# main.net
KiCad netlist of a schematic drawn in Altium Designer
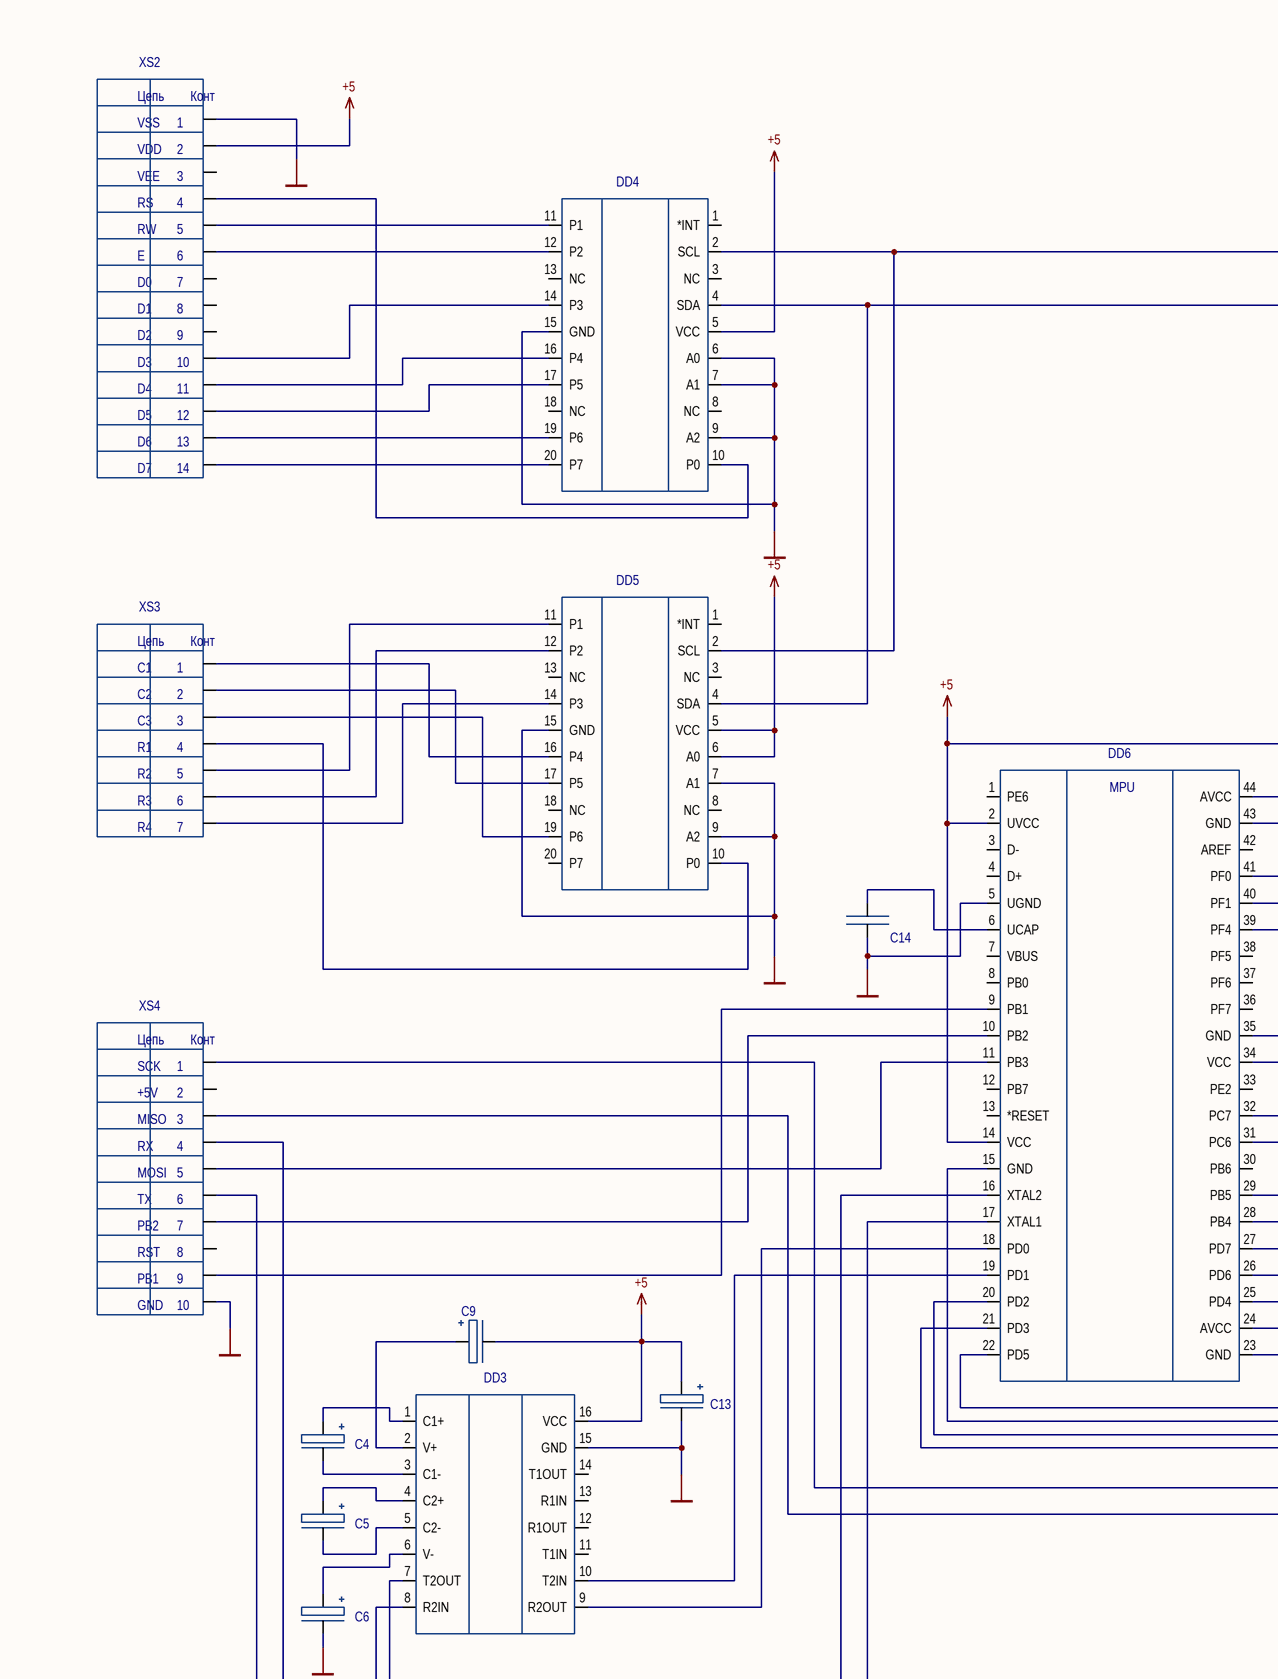
[diagram p0: main.SchDoc, top left]
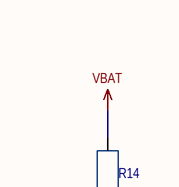
[diagram p1: main.SchDoc, top right]
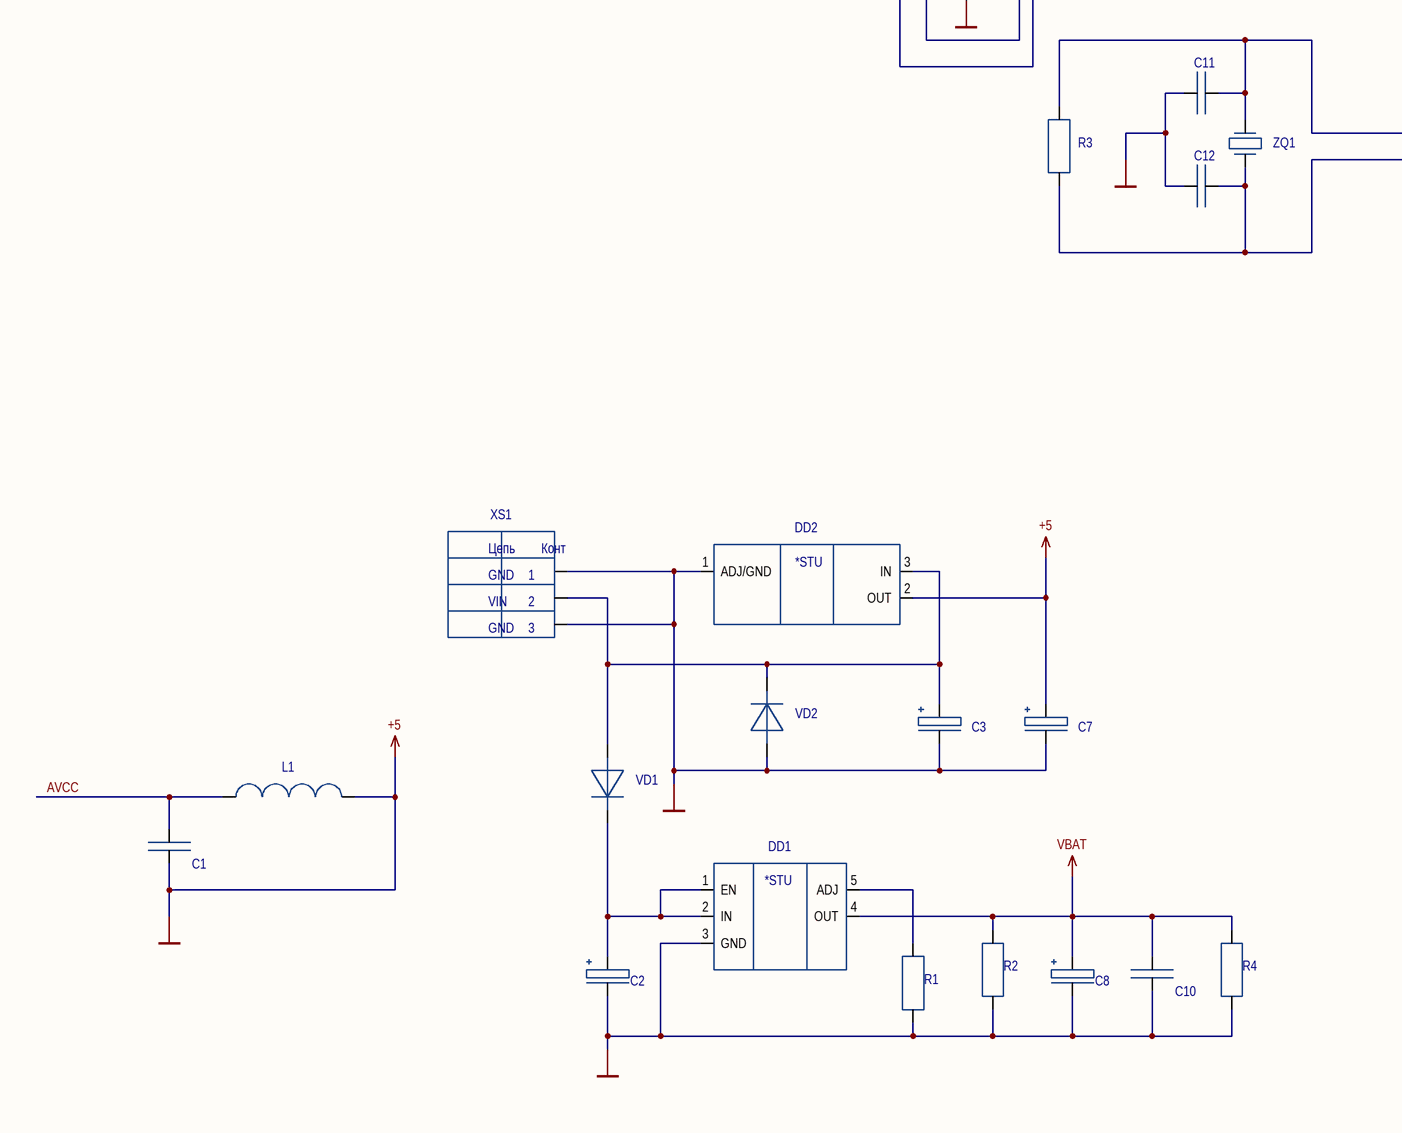
[diagram p2: main.SchDoc, bottom left]
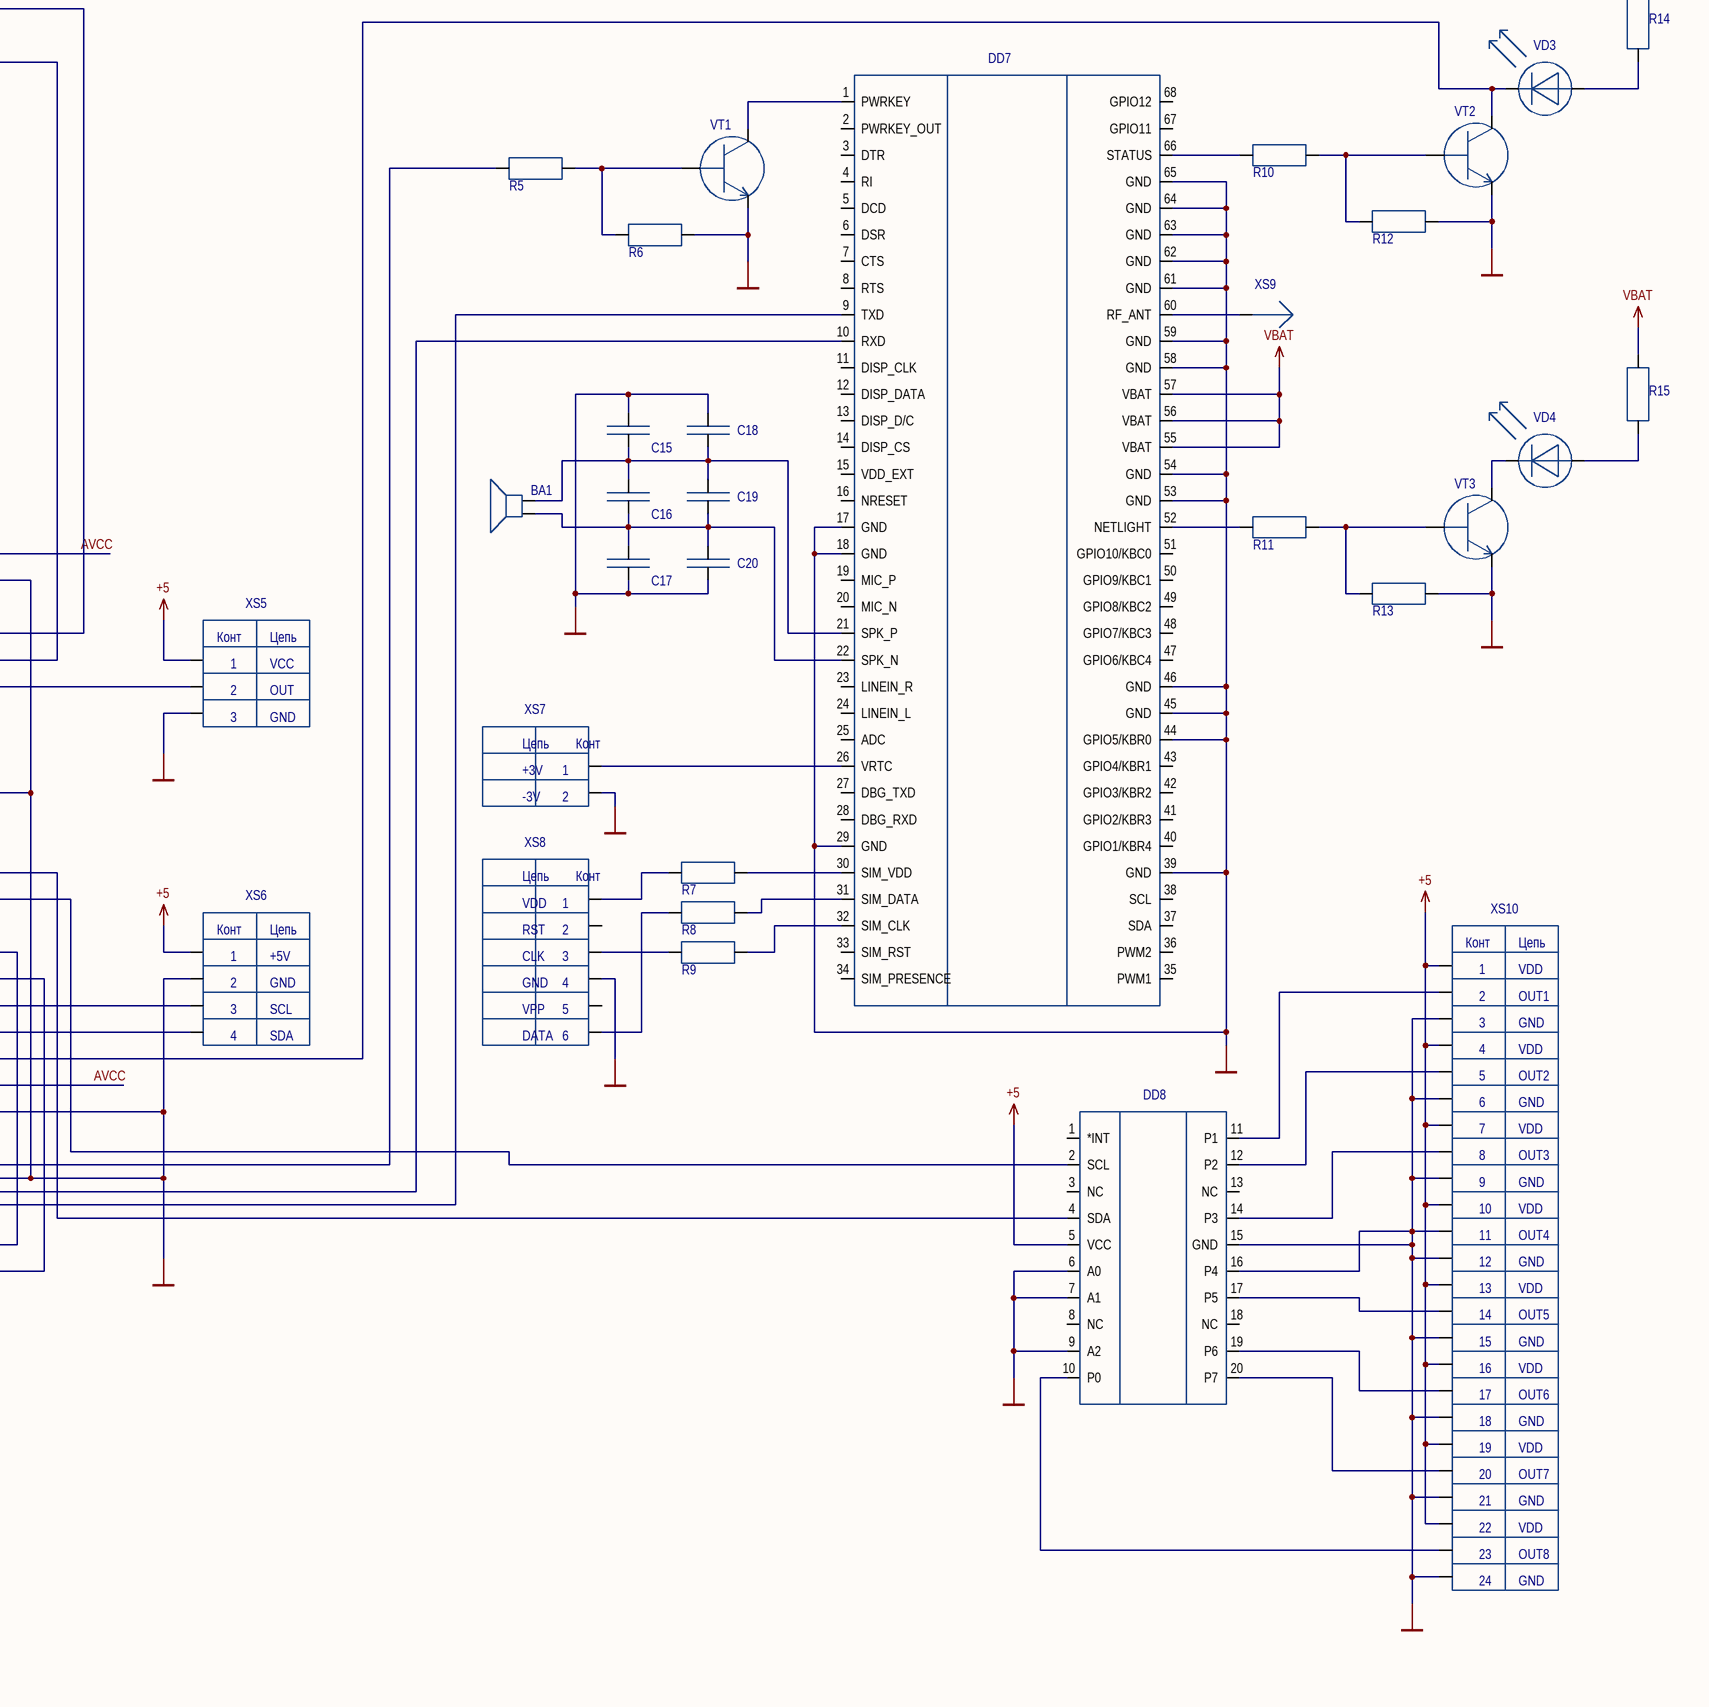
[diagram p3: main.SchDoc, bottom right]

(export (version "E")
  (design (tool "Eeschema 10.0.6"))
  (components
    (comp (ref "BA1") (value "beeper_HPA17F") (libsource (lib "diploma") (part "beeper_HPA17F")))
    (comp (ref "C1") (value "cap_1mkF") (libsource (lib "diploma") (part "cap_1mkF")))
    (comp (ref "C2") (value "cap_pol_100mkF") (libsource (lib "diploma") (part "cap_pol_100mkF")))
    (comp (ref "C3") (value "pol_10mkF") (libsource (lib "diploma") (part "cap_pol_10mkF")))
    (comp (ref "C4") (value "pol_1mkF") (libsource (lib "diploma") (part "cap_pol_1mkF")))
    (comp (ref "C5") (value "pol_1mkF") (libsource (lib "diploma") (part "cap_pol_1mkF")))
    (comp (ref "C6") (value "pol_1mkF") (libsource (lib "diploma") (part "cap_pol_1mkF")))
    (comp (ref "C7") (value "pol_10mkF") (libsource (lib "diploma") (part "cap_pol_10mkF")))
    (comp (ref "C8") (value "cap_pol_100mkF") (libsource (lib "diploma") (part "cap_pol_100mkF")))
    (comp (ref "C9") (value "pol_1mkF") (libsource (lib "diploma") (part "cap_pol_1mkF")))
    (comp (ref "C10") (value "cap_100nF") (libsource (lib "diploma") (part "cap_100nF")))
    (comp (ref "C11") (value "33pF") (libsource (lib "diploma") (part "cap_33pF")))
    (comp (ref "C12") (value "33pF") (libsource (lib "diploma") (part "cap_33pF")))
    (comp (ref "C13") (value "pol_1mkF") (libsource (lib "diploma") (part "cap_pol_1mkF")))
    (comp (ref "C14") (value "cap_1mkF") (libsource (lib "diploma") (part "cap_1mkF")))
    (comp (ref "C15") (value "cap_10pF") (libsource (lib "diploma") (part "cap_10pF")))
    (comp (ref "C16") (value "cap_10pF") (libsource (lib "diploma") (part "cap_10pF")))
    (comp (ref "C17") (value "cap_10pF") (libsource (lib "diploma") (part "cap_10pF")))
    (comp (ref "C18") (value "cap_33pF") (libsource (lib "diploma") (part "cap_33pF")))
    (comp (ref "C19") (value "cap_33pF") (libsource (lib "diploma") (part "cap_33pF")))
    (comp (ref "C20") (value "cap_33pF") (libsource (lib "diploma") (part "cap_33pF")))
    (comp (ref "DD1") (value "stu_MIC29302WT") (libsource (lib "diploma") (part "stu_MIC29302WT")))
    (comp (ref "DD2")
      (value "NCP1117ST50T3G")
      (footprint "SOT223-3_ONS")
      (description "No Description Available")
      (libsource (lib "NCP1117ST50T3G") (part "NCP1117ST50T3G"))
    )
    (comp (ref "DD3")
      (value "MAX232CSE+")
      (footprint "max232:21-0041_S16+3_MXM")
      (description "No Description Available")
      (libsource (lib "max232") (part "MAX232CSE+"))
    )
    (comp (ref "DD4")
      (value "PCF8574DGVR")
      (footprint "PCF8574DGVR:DGV20")
      (description "Remote 8-Bit I/O Expander for I2C-Bus")
      (fields
        (field (name "MANUFACTURER") "Texas Instruments")
        (field (name "GENERIC_PART_NUMBER") "PCF8574")
      )
      (libsource (lib "") (part "PCF8574DGVR_1"))
    )
    (comp (ref "DD5")
      (value "PCF8574DGVR")
      (footprint "PCF8574DGVR:DGV20")
      (description "Remote 8-Bit I/O Expander for I2C-Bus")
      (fields
        (field (name "MANUFACTURER") "Texas Instruments")
        (field (name "GENERIC_PART_NUMBER") "PCF8574")
      )
      (libsource (lib "") (part "PCF8574DGVR_1"))
    )
    (comp (ref "DD6")
      (value "ATMEGA32U4RC-AU")
      (footprint "44ML_ATM")
      (description "No Description Available")
      (libsource (lib "atmega32u4") (part "ATMEGA32U4RC-AU"))
    )
    (comp (ref "DD7") (value "SIM900A") (libsource (lib "diploma") (part "SIM900A")))
    (comp (ref "DD8")
      (value "PCF8574DGVR")
      (footprint "PCF8574DGVR:DGV20")
      (description "Remote 8-Bit I/O Expander for I2C-Bus")
      (fields
        (field (name "MANUFACTURER") "Texas Instruments")
        (field (name "GENERIC_PART_NUMBER") "PCF8574")
      )
      (libsource (lib "PCF8574DGVR") (part "PCF8574DGVR"))
    )
    (comp (ref "L1") (value "inductor_10uH") (libsource (lib "diploma") (part "inductor_10uH")))
    (comp (ref "R1") (value "res_47k") (libsource (lib "diploma") (part "res_47k")))
    (comp (ref "R2") (value "res_100K") (libsource (lib "diploma") (part "res_100K")))
    (comp (ref "R3") (value "res_1M") (libsource (lib "diploma") (part "res_1M")))
    (comp (ref "R4") (value "res_510") (libsource (lib "diploma") (part "res_510")))
    (comp (ref "R5") (value "res_4.7k") (libsource (lib "diploma") (part "res_4.7k")))
    (comp (ref "R6") (value "res_47k") (libsource (lib "") (part "res_47k_1")))
    (comp (ref "R7") (value "res_22") (libsource (lib "diploma") (part "res_22")))
    (comp (ref "R8") (value "res_22") (libsource (lib "diploma") (part "res_22")))
    (comp (ref "R9") (value "res_22") (libsource (lib "diploma") (part "res_22")))
    (comp (ref "R10") (value "res_4.7k") (libsource (lib "diploma") (part "res_4.7k")))
    (comp (ref "R11") (value "res_4.7k") (libsource (lib "diploma") (part "res_4.7k")))
    (comp (ref "R12") (value "res_47k") (libsource (lib "") (part "res_47k_1")))
    (comp (ref "R13") (value "res_47k") (libsource (lib "") (part "res_47k_1")))
    (comp (ref "R14") (value "res_510") (libsource (lib "diploma") (part "res_510")))
    (comp (ref "R15") (value "res_510") (libsource (lib "diploma") (part "res_510")))
    (comp (ref "VD1") (value "diode_M7") (libsource (lib "diploma") (part "diode_M7")))
    (comp (ref "VD2") (value "diode_M7") (libsource (lib "diploma") (part "diode_M7")))
    (comp (ref "VD3") (value "diode_red") (libsource (lib "diploma") (part "diode_red")))
    (comp (ref "VD4") (value "diode_red") (libsource (lib "diploma") (part "diode_red")))
    (comp (ref "VT1") (value "BC547") (libsource (lib "diploma") (part "BC547")))
    (comp (ref "VT2") (value "BC547") (libsource (lib "diploma") (part "BC547")))
    (comp (ref "VT3") (value "BC547") (libsource (lib "diploma") (part "BC547")))
    (comp (ref "XS1") (value "power_supply_jack") (libsource (lib "diploma") (part "power_supply_jack")))
    (comp (ref "XS2") (value "LCD_connector") (libsource (lib "diploma") (part "LCD_connector")))
    (comp (ref "XS3") (value "conn_Keypad") (libsource (lib "diploma") (part "conn_Keypad")))
    (comp (ref "XS4") (value "BH-10") (libsource (lib "diploma") (part "RS-232")))
    (comp (ref "XS5") (value "VS1833B") (libsource (lib "diploma") (part "VS1833B")))
    (comp (ref "XS6") (value "usb_typeA") (libsource (lib "diploma") (part "usb_typeA")))
    (comp (ref "XS7") (value "conn_Battery_CR2032") (libsource (lib "diploma") (part "conn_Battery_CR2032")))
    (comp (ref "XS8")
      (value "SIM5051-6-0-18-00-A")
      (footprint "sim_connector:SIM5051-6-0-18-00-A_GCT")
      (description "No Description Available")
      (libsource (lib "sim_connector") (part "SIM5051-6-0-18-00-A"))
    )
    (comp (ref "XS9") (value "antenn_connector") (libsource (lib "diploma") (part "antenn_connector")))
    (comp (ref "XS10") (value "ds1013") (libsource (lib "diploma") (part "temperature_sensors_connector")))
    (comp (ref "ZQ1") (value "crystal_8mhz") (libsource (lib "diploma") (part "crystal_8mhz")))
  )
  (nets
    (net (code "1") (name "+5") (class "Default")
      (node (ref "C1") (pin "1") (pinfunction "1_1") (pintype "passive"))
      (node (ref "C10") (pin "1") (pinfunction "1_1") (pintype "passive"))
      (node (ref "C11") (pin "2") (pinfunction "2_2") (pintype "passive"))
      (node (ref "C12") (pin "2") (pinfunction "2_2") (pintype "passive"))
      (node (ref "C13") (pin "1") (pinfunction "1_1") (pintype "passive"))
      (node (ref "C13") (pin "2") (pinfunction "2_2") (pintype "passive"))
      (node (ref "C15") (pin "2") (pinfunction "2_2") (pintype "passive"))
      (node (ref "C17") (pin "1") (pinfunction "1_1") (pintype "passive"))
      (node (ref "C18") (pin "2") (pinfunction "2_2") (pintype "passive"))
      (node (ref "C2") (pin "1") (pinfunction "1_1") (pintype "passive"))
      (node (ref "C20") (pin "1") (pinfunction "1_1") (pintype "passive"))
      (node (ref "C3") (pin "1") (pinfunction "1_1") (pintype "passive"))
      (node (ref "C6") (pin "1") (pinfunction "1_1") (pintype "passive"))
      (node (ref "C7") (pin "1") (pinfunction "1_1") (pintype "passive"))
      (node (ref "C7") (pin "2") (pinfunction "2_2") (pintype "passive"))
      (node (ref "C8") (pin "1") (pinfunction "1_1") (pintype "passive"))
      (node (ref "C9") (pin "1") (pinfunction "1_1") (pintype "passive"))
      (node (ref "DD1") (pin "3") (pinfunction "GND_3") (pintype "passive"))
      (node (ref "DD2") (pin "1") (pinfunction "ADJ/GND_1") (pintype "passive"))
      (node (ref "DD2") (pin "2") (pinfunction "OUT_2") (pintype "passive"))
      (node (ref "DD3") (pin "15") (pinfunction "GND_15") (pintype "passive"))
      (node (ref "DD3") (pin "16") (pinfunction "VCC_16") (pintype "passive"))
      (node (ref "DD4") (pin "15") (pinfunction "GND_15") (pintype "passive"))
      (node (ref "DD4") (pin "5") (pinfunction "VCC_5") (pintype "passive"))
      (node (ref "DD4") (pin "6") (pinfunction "A0_6") (pintype "passive"))
      (node (ref "DD4") (pin "7") (pinfunction "A1_7") (pintype "passive"))
      (node (ref "DD4") (pin "9") (pinfunction "A2_9") (pintype "passive"))
      (node (ref "DD5") (pin "15") (pinfunction "GND_15") (pintype "passive"))
      (node (ref "DD5") (pin "5") (pinfunction "VCC_5") (pintype "passive"))
      (node (ref "DD5") (pin "6") (pinfunction "A0_6") (pintype "passive"))
      (node (ref "DD5") (pin "7") (pinfunction "A1_7") (pintype "passive"))
      (node (ref "DD5") (pin "9") (pinfunction "A2_9") (pintype "passive"))
      (node (ref "DD6") (pin "14") (pinfunction "VCC_14") (pintype "passive"))
      (node (ref "DD6") (pin "15") (pinfunction "GND_15") (pintype "passive"))
      (node (ref "DD6") (pin "2") (pinfunction "UVCC_2") (pintype "passive"))
      (node (ref "DD6") (pin "23") (pinfunction "GND_23") (pintype "passive"))
      (node (ref "DD6") (pin "34") (pinfunction "VCC_34") (pintype "passive"))
      (node (ref "DD6") (pin "35") (pinfunction "GND_35") (pintype "passive"))
      (node (ref "DD6") (pin "43") (pinfunction "GND_43") (pintype "passive"))
      (node (ref "DD7") (pin "17") (pinfunction "GND_17") (pintype "passive"))
      (node (ref "DD7") (pin "18") (pinfunction "GND_18") (pintype "passive"))
      (node (ref "DD7") (pin "29") (pinfunction "GND_29") (pintype "passive"))
      (node (ref "DD7") (pin "39") (pinfunction "GND_39") (pintype "passive"))
      (node (ref "DD7") (pin "44") (pinfunction "GPIO5/KBR0_44") (pintype "passive"))
      (node (ref "DD7") (pin "45") (pinfunction "GND_45") (pintype "passive"))
      (node (ref "DD7") (pin "46") (pinfunction "GND_46") (pintype "passive"))
      (node (ref "DD7") (pin "53") (pinfunction "GND_53") (pintype "passive"))
      (node (ref "DD7") (pin "54") (pinfunction "GND_54") (pintype "passive"))
      (node (ref "DD7") (pin "58") (pinfunction "GND_58") (pintype "passive"))
      (node (ref "DD7") (pin "59") (pinfunction "GND_59") (pintype "passive"))
      (node (ref "DD7") (pin "61") (pinfunction "GND_61") (pintype "passive"))
      (node (ref "DD7") (pin "62") (pinfunction "GND_62") (pintype "passive"))
      (node (ref "DD7") (pin "63") (pinfunction "GND_63") (pintype "passive"))
      (node (ref "DD7") (pin "64") (pinfunction "GND_64") (pintype "passive"))
      (node (ref "DD7") (pin "65") (pinfunction "GND_65") (pintype "passive"))
      (node (ref "DD8") (pin "15") (pinfunction "GND_15") (pintype "passive"))
      (node (ref "DD8") (pin "16") (pinfunction "P4_16") (pintype "passive"))
      (node (ref "DD8") (pin "5") (pinfunction "VCC_5") (pintype "passive"))
      (node (ref "DD8") (pin "6") (pinfunction "A0_6") (pintype "passive"))
      (node (ref "DD8") (pin "7") (pinfunction "A1_7") (pintype "passive"))
      (node (ref "DD8") (pin "9") (pinfunction "A2_9") (pintype "passive"))
      (node (ref "L1") (pin "2") (pinfunction "2_2") (pintype "passive"))
      (node (ref "R1") (pin "1") (pinfunction "1_1") (pintype "passive"))
      (node (ref "R12") (pin "2") (pinfunction "2_2") (pintype "passive"))
      (node (ref "R13") (pin "2") (pinfunction "2_2") (pintype "passive"))
      (node (ref "R2") (pin "1") (pinfunction "1_1") (pintype "passive"))
      (node (ref "R4") (pin "1") (pinfunction "1_1") (pintype "passive"))
      (node (ref "R6") (pin "2") (pinfunction "2_2") (pintype "passive"))
      (node (ref "VD2") (pin "1") (pinfunction "1_1") (pintype "passive"))
      (node (ref "VT1") (pin "1") (pinfunction "E_1") (pintype "passive"))
      (node (ref "VT2") (pin "1") (pinfunction "E_1") (pintype "passive"))
      (node (ref "VT3") (pin "1") (pinfunction "E_1") (pintype "passive"))
      (node (ref "XS1") (pin "1") (pinfunction "+5V_1") (pintype "passive"))
      (node (ref "XS1") (pin "3") (pinfunction "SCL_3") (pintype "passive"))
      (node (ref "XS10") (pin "1") (pinfunction "VSS_1") (pintype "passive"))
      (node (ref "XS10") (pin "10") (pinfunction "D3_10") (pintype "passive"))
      (node (ref "XS10") (pin "11") (pinfunction "D4_11") (pintype "passive"))
      (node (ref "XS10") (pin "12") (pinfunction "D5_12") (pintype "passive"))
      (node (ref "XS10") (pin "13") (pinfunction "D6_13") (pintype "passive"))
      (node (ref "XS10") (pin "15") (pinfunction "15_15") (pintype "passive"))
      (node (ref "XS10") (pin "16") (pinfunction "16_16") (pintype "passive"))
      (node (ref "XS10") (pin "18") (pinfunction "18_18") (pintype "passive"))
      (node (ref "XS10") (pin "19") (pinfunction "19_19") (pintype "passive"))
      (node (ref "XS10") (pin "21") (pinfunction "21_21") (pintype "passive"))
      (node (ref "XS10") (pin "22") (pinfunction "22_22") (pintype "passive"))
      (node (ref "XS10") (pin "24") (pinfunction "24_24") (pintype "passive"))
      (node (ref "XS10") (pin "3") (pinfunction "VO_3") (pintype "passive"))
      (node (ref "XS10") (pin "4") (pinfunction "C/D_4") (pintype "passive"))
      (node (ref "XS10") (pin "6") (pinfunction "*WR_6") (pintype "passive"))
      (node (ref "XS10") (pin "7") (pinfunction "D0_7") (pintype "passive"))
      (node (ref "XS10") (pin "9") (pinfunction "D2_9") (pintype "passive"))
      (node (ref "XS2") (pin "1") (pinfunction "VSS_1") (pintype "passive"))
      (node (ref "XS2") (pin "2") (pinfunction "VDD_2") (pintype "passive"))
      (node (ref "XS4") (pin "10") (pinfunction "D3_10") (pintype "passive"))
      (node (ref "XS5") (pin "1") (pinfunction "VCC_1") (pintype "passive"))
      (node (ref "XS5") (pin "3") (pinfunction "GND_3") (pintype "passive"))
      (node (ref "XS6") (pin "1") (pinfunction "+5V_1") (pintype "passive"))
      (node (ref "XS6") (pin "2") (pinfunction "GND_2") (pintype "passive"))
      (node (ref "XS7") (pin "2") (pinfunction "2_2") (pintype "passive"))
      (node (ref "XS8") (pin "4") (pinfunction "GND_4") (pintype "passive"))
    )
    (net (code "2") (name "/AVCC") (class "Default")
      (node (ref "C1") (pin "2") (pinfunction "2_2") (pintype "passive"))
      (node (ref "DD6") (pin "24") (pinfunction "AVCC_24") (pintype "passive"))
      (node (ref "DD6") (pin "44") (pinfunction "AVCC_44") (pintype "passive"))
      (node (ref "L1") (pin "1") (pinfunction "1_1") (pintype "passive"))
    )
    (net (code "3") (name "Net-(DD1-ADJ)") (class "Default")
      (node (ref "DD1") (pin "5") (pinfunction "ADJ_5") (pintype "passive"))
      (node (ref "R1") (pin "2") (pinfunction "2_2") (pintype "passive"))
    )
    (net (code "4") (name "Net-(DD1-EN)") (class "Default")
      (node (ref "C2") (pin "2") (pinfunction "2_2") (pintype "passive"))
      (node (ref "DD1") (pin "1") (pinfunction "EN_1") (pintype "passive"))
      (node (ref "DD1") (pin "2") (pinfunction "IN_2") (pintype "passive"))
      (node (ref "VD1") (pin "2") (pinfunction "2_2") (pintype "passive"))
    )
    (net (code "5") (name "Net-(DD2-IN)") (class "Default")
      (node (ref "C3") (pin "2") (pinfunction "2_2") (pintype "passive"))
      (node (ref "DD2") (pin "3") (pinfunction "IN_3") (pintype "passive"))
      (node (ref "VD1") (pin "1") (pinfunction "1_1") (pintype "passive"))
      (node (ref "VD2") (pin "2") (pinfunction "2_2") (pintype "passive"))
      (node (ref "XS1") (pin "2") (pinfunction "GND_2") (pintype "passive"))
    )
    (net (code "6") (name "Net-(DD3-C1+)") (class "Default")
      (node (ref "C4") (pin "2") (pinfunction "2_2") (pintype "passive"))
      (node (ref "DD3") (pin "1") (pinfunction "C1+_1") (pintype "passive"))
    )
    (net (code "7") (name "Net-(DD3-C1-)") (class "Default")
      (node (ref "C4") (pin "1") (pinfunction "1_1") (pintype "passive"))
      (node (ref "DD3") (pin "3") (pinfunction "C1-_3") (pintype "passive"))
    )
    (net (code "8") (name "Net-(DD3-C2+)") (class "Default")
      (node (ref "C5") (pin "2") (pinfunction "2_2") (pintype "passive"))
      (node (ref "DD3") (pin "4") (pinfunction "C2+_4") (pintype "passive"))
    )
    (net (code "9") (name "Net-(DD3-C2-)") (class "Default")
      (node (ref "C5") (pin "1") (pinfunction "1_1") (pintype "passive"))
      (node (ref "DD3") (pin "5") (pinfunction "C2-_5") (pintype "passive"))
    )
    (net (code "10") (name "Net-(DD3-R2IN)") (class "Default")
      (node (ref "DD3") (pin "8") (pinfunction "R2IN_8") (pintype "passive"))
      (node (ref "XS4") (pin "4") (pinfunction "C/D_4") (pintype "passive"))
    )
    (net (code "11") (name "Net-(DD3-R2OUT)") (class "Default")
      (node (ref "DD3") (pin "9") (pinfunction "R2OUT_9") (pintype "passive"))
      (node (ref "DD6") (pin "18") (pinfunction "PD0_18") (pintype "passive"))
    )
    (net (code "12") (name "Net-(DD3-T2IN)") (class "Default")
      (node (ref "DD3") (pin "10") (pinfunction "T2IN_10") (pintype "passive"))
      (node (ref "DD6") (pin "19") (pinfunction "PD1_19") (pintype "passive"))
    )
    (net (code "13") (name "Net-(DD3-T2OUT)") (class "Default")
      (node (ref "DD3") (pin "7") (pinfunction "T2OUT_7") (pintype "passive"))
      (node (ref "XS4") (pin "6") (pinfunction "*WR_6") (pintype "passive"))
    )
    (net (code "14") (name "Net-(DD3-V+)") (class "Default")
      (node (ref "C9") (pin "2") (pinfunction "2_2") (pintype "passive"))
      (node (ref "DD3") (pin "2") (pinfunction "V+_2") (pintype "passive"))
    )
    (net (code "15") (name "Net-(DD3-V-)") (class "Default")
      (node (ref "C6") (pin "2") (pinfunction "2_2") (pintype "passive"))
      (node (ref "DD3") (pin "6") (pinfunction "V-_6") (pintype "passive"))
    )
    (net (code "16") (name "Net-(DD4-P0)") (class "Default")
      (node (ref "DD4") (pin "10") (pinfunction "P0_10") (pintype "passive"))
      (node (ref "XS2") (pin "4") (pinfunction "C/D_4") (pintype "passive"))
    )
    (net (code "17") (name "Net-(DD4-P1)") (class "Default")
      (node (ref "DD4") (pin "11") (pinfunction "P1_11") (pintype "passive"))
      (node (ref "XS2") (pin "5") (pinfunction "*RD_5") (pintype "passive"))
    )
    (net (code "18") (name "Net-(DD4-P2)") (class "Default")
      (node (ref "DD4") (pin "12") (pinfunction "P2_12") (pintype "passive"))
      (node (ref "XS2") (pin "6") (pinfunction "*WR_6") (pintype "passive"))
    )
    (net (code "19") (name "Net-(DD4-P3)") (class "Default")
      (node (ref "DD4") (pin "14") (pinfunction "P3_14") (pintype "passive"))
      (node (ref "XS2") (pin "10") (pinfunction "D3_10") (pintype "passive"))
    )
    (net (code "20") (name "Net-(DD4-P4)") (class "Default")
      (node (ref "DD4") (pin "16") (pinfunction "P4_16") (pintype "passive"))
      (node (ref "XS2") (pin "11") (pinfunction "D4_11") (pintype "passive"))
    )
    (net (code "21") (name "Net-(DD4-P5)") (class "Default")
      (node (ref "DD4") (pin "17") (pinfunction "P5_17") (pintype "passive"))
      (node (ref "XS2") (pin "12") (pinfunction "D5_12") (pintype "passive"))
    )
    (net (code "22") (name "Net-(DD4-P6)") (class "Default")
      (node (ref "DD4") (pin "19") (pinfunction "P6_19") (pintype "passive"))
      (node (ref "XS2") (pin "13") (pinfunction "D6_13") (pintype "passive"))
    )
    (net (code "23") (name "Net-(DD4-P7)") (class "Default")
      (node (ref "DD4") (pin "20") (pinfunction "P7_20") (pintype "passive"))
      (node (ref "XS2") (pin "14") (pinfunction "D7_14") (pintype "passive"))
    )
    (net (code "24") (name "Net-(DD4-SCL)") (class "Default")
      (node (ref "DD4") (pin "2") (pinfunction "SCL_2") (pintype "passive"))
      (node (ref "DD5") (pin "2") (pinfunction "SCL_2") (pintype "passive"))
      (node (ref "DD6") (pin "41") (pinfunction "PF0_41") (pintype "passive"))
    )
    (net (code "25") (name "Net-(DD4-SDA)") (class "Default")
      (node (ref "DD4") (pin "4") (pinfunction "SDA_4") (pintype "passive"))
      (node (ref "DD5") (pin "4") (pinfunction "SDA_4") (pintype "passive"))
      (node (ref "DD6") (pin "40") (pinfunction "PF1_40") (pintype "passive"))
    )
    (net (code "26") (name "Net-(DD5-P0)") (class "Default")
      (node (ref "DD5") (pin "10") (pinfunction "P0_10") (pintype "passive"))
      (node (ref "XS3") (pin "4") (pinfunction "C/D_4") (pintype "passive"))
    )
    (net (code "27") (name "Net-(DD5-P1)") (class "Default")
      (node (ref "DD5") (pin "11") (pinfunction "P1_11") (pintype "passive"))
      (node (ref "XS3") (pin "5") (pinfunction "*RD_5") (pintype "passive"))
    )
    (net (code "28") (name "Net-(DD5-P2)") (class "Default")
      (node (ref "DD5") (pin "12") (pinfunction "P2_12") (pintype "passive"))
      (node (ref "XS3") (pin "6") (pinfunction "*WR_6") (pintype "passive"))
    )
    (net (code "29") (name "Net-(DD5-P3)") (class "Default")
      (node (ref "DD5") (pin "14") (pinfunction "P3_14") (pintype "passive"))
      (node (ref "XS3") (pin "7") (pinfunction "D0_7") (pintype "passive"))
    )
    (net (code "30") (name "Net-(DD5-P4)") (class "Default")
      (node (ref "DD5") (pin "16") (pinfunction "P4_16") (pintype "passive"))
      (node (ref "XS3") (pin "1") (pinfunction "VSS_1") (pintype "passive"))
    )
    (net (code "31") (name "Net-(DD5-P5)") (class "Default")
      (node (ref "DD5") (pin "17") (pinfunction "P5_17") (pintype "passive"))
      (node (ref "XS3") (pin "2") (pinfunction "VDD_2") (pintype "passive"))
    )
    (net (code "32") (name "Net-(DD5-P6)") (class "Default")
      (node (ref "DD5") (pin "19") (pinfunction "P6_19") (pintype "passive"))
      (node (ref "XS3") (pin "3") (pinfunction "VO_3") (pintype "passive"))
    )
    (net (code "33") (name "Net-(DD6-PB1)") (class "Default")
      (node (ref "DD6") (pin "9") (pinfunction "PB1_9") (pintype "passive"))
      (node (ref "XS4") (pin "9") (pinfunction "D2_9") (pintype "passive"))
    )
    (net (code "34") (name "Net-(DD6-PB2)") (class "Default")
      (node (ref "DD6") (pin "10") (pinfunction "PB2_10") (pintype "passive"))
      (node (ref "XS4") (pin "7") (pinfunction "D0_7") (pintype "passive"))
    )
    (net (code "35") (name "Net-(DD6-PB3)") (class "Default")
      (node (ref "DD6") (pin "11") (pinfunction "PB3_11") (pintype "passive"))
      (node (ref "XS4") (pin "5") (pinfunction "*RD_5") (pintype "passive"))
    )
    (net (code "36") (name "Net-(DD6-PB4)") (class "Default")
      (node (ref "DD6") (pin "28") (pinfunction "PB4_28") (pintype "passive"))
      (node (ref "XS4") (pin "3") (pinfunction "VO_3") (pintype "passive"))
    )
    (net (code "37") (name "Net-(DD6-PB5)") (class "Default")
      (node (ref "DD6") (pin "29") (pinfunction "PB5_29") (pintype "passive"))
      (node (ref "XS4") (pin "1") (pinfunction "VSS_1") (pintype "passive"))
    )
    (net (code "38") (name "Net-(DD6-PC6)") (class "Default")
      (node (ref "DD6") (pin "31") (pinfunction "PC6_31") (pintype "passive"))
      (node (ref "DD8") (pin "2") (pinfunction "SCL_2") (pintype "passive"))
    )
    (net (code "39") (name "Net-(DD6-PC7)") (class "Default")
      (node (ref "DD6") (pin "32") (pinfunction "PC7_32") (pintype "passive"))
      (node (ref "DD8") (pin "4") (pinfunction "SDA_4") (pintype "passive"))
    )
    (net (code "40") (name "Net-(DD6-PD2)") (class "Default")
      (node (ref "DD6") (pin "20") (pinfunction "PD2_20") (pintype "passive"))
      (node (ref "DD7") (pin "10") (pinfunction "RXD_10") (pintype "passive"))
    )
    (net (code "41") (name "Net-(DD6-PD3)") (class "Default")
      (node (ref "DD6") (pin "21") (pinfunction "PD3_21") (pintype "passive"))
      (node (ref "DD7") (pin "9") (pinfunction "TXD_9") (pintype "passive"))
    )
    (net (code "42") (name "Net-(DD6-PD4)") (class "Default")
      (node (ref "DD6") (pin "25") (pinfunction "PD4_25") (pintype "passive"))
      (node (ref "VD3") (pin "2") (pinfunction "2_2") (pintype "passive"))
      (node (ref "VT2") (pin "3") (pinfunction "C_3") (pintype "passive"))
    )
    (net (code "43") (name "Net-(DD6-PD5)") (class "Default")
      (node (ref "DD6") (pin "22") (pinfunction "PD5_22") (pintype "passive"))
      (node (ref "R5") (pin "1") (pinfunction "1_1") (pintype "passive"))
    )
    (net (code "44") (name "Net-(DD6-PD6)") (class "Default")
      (node (ref "DD6") (pin "26") (pinfunction "PD6_26") (pintype "passive"))
      (node (ref "XS6") (pin "4") (pinfunction "SDA_4") (pintype "passive"))
    )
    (net (code "45") (name "Net-(DD6-PD7)") (class "Default")
      (node (ref "DD6") (pin "27") (pinfunction "PD7_27") (pintype "passive"))
      (node (ref "XS6") (pin "3") (pinfunction "SCL_3") (pintype "passive"))
    )
    (net (code "46") (name "Net-(DD6-PF4)") (class "Default")
      (node (ref "DD6") (pin "39") (pinfunction "PF4_39") (pintype "passive"))
      (node (ref "XS5") (pin "2") (pinfunction "OUT_2") (pintype "passive"))
    )
    (net (code "47") (name "Net-(DD6-UCAP)") (class "Default")
      (node (ref "C14") (pin "2") (pinfunction "2_2") (pintype "passive"))
      (node (ref "DD6") (pin "6") (pinfunction "UCAP_6") (pintype "passive"))
    )
    (net (code "48") (name "Net-(DD6-XTAL1)") (class "Default")
      (node (ref "C12") (pin "1") (pinfunction "1_1") (pintype "passive"))
      (node (ref "DD6") (pin "17") (pinfunction "XTAL1_17") (pintype "passive"))
      (node (ref "R3") (pin "1") (pinfunction "1_1") (pintype "passive"))
      (node (ref "ZQ1") (pin "1") (pinfunction "1_1") (pintype "passive"))
    )
    (net (code "49") (name "Net-(DD6-XTAL2)") (class "Default")
      (node (ref "C11") (pin "1") (pinfunction "1_1") (pintype "passive"))
      (node (ref "DD6") (pin "16") (pinfunction "XTAL2_16") (pintype "passive"))
      (node (ref "R3") (pin "2") (pinfunction "2_2") (pintype "passive"))
      (node (ref "ZQ1") (pin "2") (pinfunction "2_2") (pintype "passive"))
    )
    (net (code "50") (name "Net-(DD7-NETLIGHT)") (class "Default")
      (node (ref "DD7") (pin "52") (pinfunction "NETLIGHT_52") (pintype "passive"))
      (node (ref "R11") (pin "1") (pinfunction "1_1") (pintype "passive"))
    )
    (net (code "51") (name "Net-(DD7-PWRKEY)") (class "Default")
      (node (ref "DD7") (pin "1") (pinfunction "PWRKEY_1") (pintype "passive"))
      (node (ref "VT1") (pin "3") (pinfunction "C_3") (pintype "passive"))
    )
    (net (code "52") (name "Net-(DD7-RF_ANT)") (class "Default")
      (node (ref "DD7") (pin "60") (pinfunction "RF_ANT_60") (pintype "passive"))
      (node (ref "XS9") (pin "1") (pinfunction "1_1") (pintype "passive"))
    )
    (net (code "53") (name "Net-(DD7-SIM_CLK)") (class "Default")
      (node (ref "DD7") (pin "32") (pinfunction "SIM_CLK_32") (pintype "passive"))
      (node (ref "R9") (pin "2") (pinfunction "2_2") (pintype "passive"))
    )
    (net (code "54") (name "Net-(DD7-SIM_DATA)") (class "Default")
      (node (ref "DD7") (pin "31") (pinfunction "SIM_DATA_31") (pintype "passive"))
      (node (ref "R8") (pin "2") (pinfunction "2_2") (pintype "passive"))
    )
    (net (code "55") (name "Net-(DD7-SIM_VDD)") (class "Default")
      (node (ref "DD7") (pin "30") (pinfunction "SIM_VDD_30") (pintype "passive"))
      (node (ref "R7") (pin "2") (pinfunction "2_2") (pintype "passive"))
    )
    (net (code "56") (name "Net-(DD7-SPK_N)") (class "Default")
      (node (ref "BA1") (pin "2") (pinfunction "2_2") (pintype "passive"))
      (node (ref "C16") (pin "1") (pinfunction "1_1") (pintype "passive"))
      (node (ref "C17") (pin "2") (pinfunction "2_2") (pintype "passive"))
      (node (ref "C19") (pin "1") (pinfunction "1_1") (pintype "passive"))
      (node (ref "C20") (pin "2") (pinfunction "2_2") (pintype "passive"))
      (node (ref "DD7") (pin "22") (pinfunction "SPK_N_22") (pintype "passive"))
    )
    (net (code "57") (name "Net-(DD7-SPK_P)") (class "Default")
      (node (ref "BA1") (pin "1") (pinfunction "1_1") (pintype "passive"))
      (node (ref "C15") (pin "1") (pinfunction "1_1") (pintype "passive"))
      (node (ref "C16") (pin "2") (pinfunction "2_2") (pintype "passive"))
      (node (ref "C18") (pin "1") (pinfunction "1_1") (pintype "passive"))
      (node (ref "C19") (pin "2") (pinfunction "2_2") (pintype "passive"))
      (node (ref "DD7") (pin "21") (pinfunction "SPK_P_21") (pintype "passive"))
    )
    (net (code "58") (name "Net-(DD7-STATUS)") (class "Default")
      (node (ref "DD7") (pin "66") (pinfunction "STATUS_66") (pintype "passive"))
      (node (ref "R10") (pin "1") (pinfunction "1_1") (pintype "passive"))
    )
    (net (code "59") (name "Net-(DD7-VRTC)") (class "Default")
      (node (ref "DD7") (pin "26") (pinfunction "VRTC_26") (pintype "passive"))
      (node (ref "XS7") (pin "1") (pinfunction "VCC_1") (pintype "passive"))
    )
    (net (code "60") (name "Net-(DD8-P0)") (class "Default")
      (node (ref "DD8") (pin "10") (pinfunction "P0_10") (pintype "passive"))
      (node (ref "XS10") (pin "23") (pinfunction "23_23") (pintype "passive"))
    )
    (net (code "61") (name "Net-(DD8-P1)") (class "Default")
      (node (ref "DD8") (pin "11") (pinfunction "P1_11") (pintype "passive"))
      (node (ref "XS10") (pin "2") (pinfunction "VDD_2") (pintype "passive"))
    )
    (net (code "62") (name "Net-(DD8-P2)") (class "Default")
      (node (ref "DD8") (pin "12") (pinfunction "P2_12") (pintype "passive"))
      (node (ref "XS10") (pin "5") (pinfunction "*RD_5") (pintype "passive"))
    )
    (net (code "63") (name "Net-(DD8-P3)") (class "Default")
      (node (ref "DD8") (pin "14") (pinfunction "P3_14") (pintype "passive"))
      (node (ref "XS10") (pin "8") (pinfunction "D1_8") (pintype "passive"))
    )
    (net (code "64") (name "Net-(DD8-P5)") (class "Default")
      (node (ref "DD8") (pin "17") (pinfunction "P5_17") (pintype "passive"))
      (node (ref "XS10") (pin "14") (pinfunction "D7_14") (pintype "passive"))
    )
    (net (code "65") (name "Net-(DD8-P6)") (class "Default")
      (node (ref "DD8") (pin "19") (pinfunction "P6_19") (pintype "passive"))
      (node (ref "XS10") (pin "17") (pinfunction "17_17") (pintype "passive"))
    )
    (net (code "66") (name "Net-(DD8-P7)") (class "Default")
      (node (ref "DD8") (pin "20") (pinfunction "P7_20") (pintype "passive"))
      (node (ref "XS10") (pin "20") (pinfunction "20_20") (pintype "passive"))
    )
    (net (code "67") (name "Net-(R14-Pad1)") (class "Default")
      (node (ref "R14") (pin "1") (pinfunction "1_1") (pintype "passive"))
      (node (ref "VD3") (pin "1") (pinfunction "1_1") (pintype "passive"))
    )
    (net (code "68") (name "Net-(R15-Pad1)") (class "Default")
      (node (ref "R15") (pin "1") (pinfunction "1_1") (pintype "passive"))
      (node (ref "VD4") (pin "1") (pinfunction "1_1") (pintype "passive"))
    )
    (net (code "69") (name "Net-(VT1-B)") (class "Default")
      (node (ref "R5") (pin "2") (pinfunction "2_2") (pintype "passive"))
      (node (ref "R6") (pin "1") (pinfunction "1_1") (pintype "passive"))
      (node (ref "VT1") (pin "2") (pinfunction "B_2") (pintype "passive"))
    )
    (net (code "70") (name "Net-(VT2-B)") (class "Default")
      (node (ref "R10") (pin "2") (pinfunction "2_2") (pintype "passive"))
      (node (ref "R12") (pin "1") (pinfunction "1_1") (pintype "passive"))
      (node (ref "VT2") (pin "2") (pinfunction "B_2") (pintype "passive"))
    )
    (net (code "71") (name "Net-(VT3-B)") (class "Default")
      (node (ref "R11") (pin "2") (pinfunction "2_2") (pintype "passive"))
      (node (ref "R13") (pin "1") (pinfunction "1_1") (pintype "passive"))
      (node (ref "VT3") (pin "2") (pinfunction "B_2") (pintype "passive"))
    )
    (net (code "72") (name "Net-(VT3-C)") (class "Default")
      (node (ref "VD4") (pin "2") (pinfunction "2_2") (pintype "passive"))
      (node (ref "VT3") (pin "3") (pinfunction "C_3") (pintype "passive"))
    )
    (net (code "73") (name "Net-(XS8-CLK)") (class "Default")
      (node (ref "R9") (pin "1") (pinfunction "1_1") (pintype "passive"))
      (node (ref "XS8") (pin "3") (pinfunction "CLK_3") (pintype "passive"))
    )
    (net (code "74") (name "Net-(XS8-I{slash}O)") (class "Default")
      (node (ref "R8") (pin "1") (pinfunction "1_1") (pintype "passive"))
      (node (ref "XS8") (pin "6") (pinfunction "I/O_6") (pintype "passive"))
    )
    (net (code "75") (name "Net-(XS8-VCC)") (class "Default")
      (node (ref "R7") (pin "1") (pinfunction "1_1") (pintype "passive"))
      (node (ref "XS8") (pin "1") (pinfunction "VCC_1") (pintype "power_in"))
    )
    (net (code "76") (name "UGND") (class "Default")
      (node (ref "C14") (pin "1") (pinfunction "1_1") (pintype "passive"))
      (node (ref "DD6") (pin "5") (pinfunction "UGND_5") (pintype "passive"))
    )
    (net (code "77") (name "VBAT") (class "Default")
      (node (ref "C10") (pin "2") (pinfunction "2_2") (pintype "passive"))
      (node (ref "C8") (pin "2") (pinfunction "2_2") (pintype "passive"))
      (node (ref "DD1") (pin "4") (pinfunction "OUT_4") (pintype "passive"))
      (node (ref "DD7") (pin "55") (pinfunction "VBAT_55") (pintype "passive"))
      (node (ref "DD7") (pin "56") (pinfunction "VBAT_56") (pintype "passive"))
      (node (ref "DD7") (pin "57") (pinfunction "VBAT_57") (pintype "passive"))
      (node (ref "R14") (pin "2") (pinfunction "2_2") (pintype "passive"))
      (node (ref "R15") (pin "2") (pinfunction "2_2") (pintype "passive"))
      (node (ref "R2") (pin "2") (pinfunction "2_2") (pintype "passive"))
      (node (ref "R4") (pin "2") (pinfunction "2_2") (pintype "passive"))
    )
    (net (code "78") (name "unconnected-(DD3-R1IN-Pad13)") (class "Default")
      (node (ref "DD3") (pin "13") (pinfunction "R1IN_13") (pintype "passive"))
    )
    (net (code "79") (name "unconnected-(DD3-R1OUT-Pad12)") (class "Default")
      (node (ref "DD3") (pin "12") (pinfunction "R1OUT_12") (pintype "passive"))
    )
    (net (code "80") (name "unconnected-(DD3-T1IN-Pad11)") (class "Default")
      (node (ref "DD3") (pin "11") (pinfunction "T1IN_11") (pintype "passive"))
    )
    (net (code "81") (name "unconnected-(DD3-T1OUT-Pad14)") (class "Default")
      (node (ref "DD3") (pin "14") (pinfunction "T1OUT_14") (pintype "passive"))
    )
    (net (code "82") (name "unconnected-(DD4-*INT-Pad1)") (class "Default")
      (node (ref "DD4") (pin "1") (pinfunction "*INT_1") (pintype "passive"))
    )
    (net (code "83") (name "unconnected-(DD4-NC-Pad3)") (class "Default")
      (node (ref "DD4") (pin "3") (pinfunction "NC_3") (pintype "passive"))
    )
    (net (code "84") (name "unconnected-(DD4-NC-Pad8)") (class "Default")
      (node (ref "DD4") (pin "8") (pinfunction "NC_8") (pintype "passive"))
    )
    (net (code "85") (name "unconnected-(DD4-NC-Pad13)") (class "Default")
      (node (ref "DD4") (pin "13") (pinfunction "NC_13") (pintype "passive"))
    )
    (net (code "86") (name "unconnected-(DD4-NC-Pad18)") (class "Default")
      (node (ref "DD4") (pin "18") (pinfunction "NC_18") (pintype "passive"))
    )
    (net (code "87") (name "unconnected-(DD5-*INT-Pad1)") (class "Default")
      (node (ref "DD5") (pin "1") (pinfunction "*INT_1") (pintype "passive"))
    )
    (net (code "88") (name "unconnected-(DD5-NC-Pad3)") (class "Default")
      (node (ref "DD5") (pin "3") (pinfunction "NC_3") (pintype "passive"))
    )
    (net (code "89") (name "unconnected-(DD5-NC-Pad8)") (class "Default")
      (node (ref "DD5") (pin "8") (pinfunction "NC_8") (pintype "passive"))
    )
    (net (code "90") (name "unconnected-(DD5-NC-Pad13)") (class "Default")
      (node (ref "DD5") (pin "13") (pinfunction "NC_13") (pintype "passive"))
    )
    (net (code "91") (name "unconnected-(DD5-NC-Pad18)") (class "Default")
      (node (ref "DD5") (pin "18") (pinfunction "NC_18") (pintype "passive"))
    )
    (net (code "92") (name "unconnected-(DD5-P7-Pad20)") (class "Default")
      (node (ref "DD5") (pin "20") (pinfunction "P7_20") (pintype "passive"))
    )
    (net (code "93") (name "unconnected-(DD6-*RESET-Pad13)") (class "Default")
      (node (ref "DD6") (pin "13") (pinfunction "*RESET_13") (pintype "passive"))
    )
    (net (code "94") (name "unconnected-(DD6-AREF-Pad42)") (class "Default")
      (node (ref "DD6") (pin "42") (pinfunction "AREF_42") (pintype "passive"))
    )
    (net (code "95") (name "unconnected-(DD6-D+-Pad4)") (class "Default")
      (node (ref "DD6") (pin "4") (pinfunction "D+_4") (pintype "passive"))
    )
    (net (code "96") (name "unconnected-(DD6-D--Pad3)") (class "Default")
      (node (ref "DD6") (pin "3") (pinfunction "D-_3") (pintype "passive"))
    )
    (net (code "97") (name "unconnected-(DD6-PB0-Pad8)") (class "Default")
      (node (ref "DD6") (pin "8") (pinfunction "PB0_8") (pintype "passive"))
    )
    (net (code "98") (name "unconnected-(DD6-PB6-Pad30)") (class "Default")
      (node (ref "DD6") (pin "30") (pinfunction "PB6_30") (pintype "passive"))
    )
    (net (code "99") (name "unconnected-(DD6-PB7-Pad12)") (class "Default")
      (node (ref "DD6") (pin "12") (pinfunction "PB7_12") (pintype "passive"))
    )
    (net (code "100") (name "unconnected-(DD6-PE2-Pad33)") (class "Default")
      (node (ref "DD6") (pin "33") (pinfunction "PE2_33") (pintype "passive"))
    )
    (net (code "101") (name "unconnected-(DD6-PE6-Pad1)") (class "Default")
      (node (ref "DD6") (pin "1") (pinfunction "PE6_1") (pintype "passive"))
    )
    (net (code "102") (name "unconnected-(DD6-PF5-Pad38)") (class "Default")
      (node (ref "DD6") (pin "38") (pinfunction "PF5_38") (pintype "passive"))
    )
    (net (code "103") (name "unconnected-(DD6-PF6-Pad37)") (class "Default")
      (node (ref "DD6") (pin "37") (pinfunction "PF6_37") (pintype "passive"))
    )
    (net (code "104") (name "unconnected-(DD6-PF7-Pad36)") (class "Default")
      (node (ref "DD6") (pin "36") (pinfunction "PF7_36") (pintype "passive"))
    )
    (net (code "105") (name "unconnected-(DD6-VBUS-Pad7)") (class "Default")
      (node (ref "DD6") (pin "7") (pinfunction "VBUS_7") (pintype "passive"))
    )
    (net (code "106") (name "unconnected-(DD7-ADC-Pad25)") (class "Default")
      (node (ref "DD7") (pin "25") (pinfunction "ADC_25") (pintype "passive"))
    )
    (net (code "107") (name "unconnected-(DD7-CTS-Pad7)") (class "Default")
      (node (ref "DD7") (pin "7") (pinfunction "CTS_7") (pintype "passive"))
    )
    (net (code "108") (name "unconnected-(DD7-DBG_RXD-Pad28)") (class "Default")
      (node (ref "DD7") (pin "28") (pinfunction "DBG_RXD_28") (pintype "passive"))
    )
    (net (code "109") (name "unconnected-(DD7-DBG_TXD-Pad27)") (class "Default")
      (node (ref "DD7") (pin "27") (pinfunction "DBG_TXD_27") (pintype "passive"))
    )
    (net (code "110") (name "unconnected-(DD7-DCD-Pad5)") (class "Default")
      (node (ref "DD7") (pin "5") (pinfunction "DCD_5") (pintype "passive"))
    )
    (net (code "111") (name "unconnected-(DD7-DISP_CLK-Pad11)") (class "Default")
      (node (ref "DD7") (pin "11") (pinfunction "DISP_CLK_11") (pintype "passive"))
    )
    (net (code "112") (name "unconnected-(DD7-DISP_CS-Pad14)") (class "Default")
      (node (ref "DD7") (pin "14") (pinfunction "DISP_CS_14") (pintype "passive"))
    )
    (net (code "113") (name "unconnected-(DD7-DISP_DATA-Pad12)") (class "Default")
      (node (ref "DD7") (pin "12") (pinfunction "DISP_DATA_12") (pintype "passive"))
    )
    (net (code "114") (name "unconnected-(DD7-DISP_D{slash}C-Pad13)") (class "Default")
      (node (ref "DD7") (pin "13") (pinfunction "DISP_D/C_13") (pintype "passive"))
    )
    (net (code "115") (name "unconnected-(DD7-DSR-Pad6)") (class "Default")
      (node (ref "DD7") (pin "6") (pinfunction "DSR_6") (pintype "passive"))
    )
    (net (code "116") (name "unconnected-(DD7-DTR-Pad3)") (class "Default")
      (node (ref "DD7") (pin "3") (pinfunction "DTR_3") (pintype "passive"))
    )
    (net (code "117") (name "unconnected-(DD7-GPIO1{slash}KBR4-Pad40)") (class "Default")
      (node (ref "DD7") (pin "40") (pinfunction "GPIO1/KBR4_40") (pintype "passive"))
    )
    (net (code "118") (name "unconnected-(DD7-GPIO2{slash}KBR3-Pad41)") (class "Default")
      (node (ref "DD7") (pin "41") (pinfunction "GPIO2/KBR3_41") (pintype "passive"))
    )
    (net (code "119") (name "unconnected-(DD7-GPIO3{slash}KBR2-Pad42)") (class "Default")
      (node (ref "DD7") (pin "42") (pinfunction "GPIO3/KBR2_42") (pintype "passive"))
    )
    (net (code "120") (name "unconnected-(DD7-GPIO4{slash}KBR1-Pad43)") (class "Default")
      (node (ref "DD7") (pin "43") (pinfunction "GPIO4/KBR1_43") (pintype "passive"))
    )
    (net (code "121") (name "unconnected-(DD7-GPIO6{slash}KBC4-Pad47)") (class "Default")
      (node (ref "DD7") (pin "47") (pinfunction "GPIO6/KBC4_47") (pintype "passive"))
    )
    (net (code "122") (name "unconnected-(DD7-GPIO7{slash}KBC3-Pad48)") (class "Default")
      (node (ref "DD7") (pin "48") (pinfunction "GPIO7/KBC3_48") (pintype "passive"))
    )
    (net (code "123") (name "unconnected-(DD7-GPIO8{slash}KBC2-Pad49)") (class "Default")
      (node (ref "DD7") (pin "49") (pinfunction "GPIO8/KBC2_49") (pintype "passive"))
    )
    (net (code "124") (name "unconnected-(DD7-GPIO9{slash}KBC1-Pad50)") (class "Default")
      (node (ref "DD7") (pin "50") (pinfunction "GPIO9/KBC1_50") (pintype "passive"))
    )
    (net (code "125") (name "unconnected-(DD7-GPIO10{slash}KBC0-Pad51)") (class "Default")
      (node (ref "DD7") (pin "51") (pinfunction "GPIO10/KBC0_51") (pintype "passive"))
    )
    (net (code "126") (name "unconnected-(DD7-GPIO11-Pad67)") (class "Default")
      (node (ref "DD7") (pin "67") (pinfunction "GPIO11_67") (pintype "passive"))
    )
    (net (code "127") (name "unconnected-(DD7-GPIO12-Pad68)") (class "Default")
      (node (ref "DD7") (pin "68") (pinfunction "GPIO12_68") (pintype "passive"))
    )
    (net (code "128") (name "unconnected-(DD7-LINEIN_L-Pad24)") (class "Default")
      (node (ref "DD7") (pin "24") (pinfunction "LINEIN_L_24") (pintype "passive"))
    )
    (net (code "129") (name "unconnected-(DD7-LINEIN_R-Pad23)") (class "Default")
      (node (ref "DD7") (pin "23") (pinfunction "LINEIN_R_23") (pintype "passive"))
    )
    (net (code "130") (name "unconnected-(DD7-MIC_N-Pad20)") (class "Default")
      (node (ref "DD7") (pin "20") (pinfunction "MIC_N_20") (pintype "passive"))
    )
    (net (code "131") (name "unconnected-(DD7-MIC_P-Pad19)") (class "Default")
      (node (ref "DD7") (pin "19") (pinfunction "MIC_P_19") (pintype "passive"))
    )
    (net (code "132") (name "unconnected-(DD7-NRESET-Pad16)") (class "Default")
      (node (ref "DD7") (pin "16") (pinfunction "NRESET_16") (pintype "passive"))
    )
    (net (code "133") (name "unconnected-(DD7-PWM1-Pad35)") (class "Default")
      (node (ref "DD7") (pin "35") (pinfunction "PWM1_35") (pintype "passive"))
    )
    (net (code "134") (name "unconnected-(DD7-PWM2-Pad36)") (class "Default")
      (node (ref "DD7") (pin "36") (pinfunction "PWM2_36") (pintype "passive"))
    )
    (net (code "135") (name "unconnected-(DD7-PWRKEY_OUT-Pad2)") (class "Default")
      (node (ref "DD7") (pin "2") (pinfunction "PWRKEY_OUT_2") (pintype "passive"))
    )
    (net (code "136") (name "unconnected-(DD7-RI-Pad4)") (class "Default")
      (node (ref "DD7") (pin "4") (pinfunction "RI_4") (pintype "passive"))
    )
    (net (code "137") (name "unconnected-(DD7-RTS-Pad8)") (class "Default")
      (node (ref "DD7") (pin "8") (pinfunction "RTS_8") (pintype "passive"))
    )
    (net (code "138") (name "unconnected-(DD7-SCL-Pad38)") (class "Default")
      (node (ref "DD7") (pin "38") (pinfunction "SCL_38") (pintype "passive"))
    )
    (net (code "139") (name "unconnected-(DD7-SDA-Pad37)") (class "Default")
      (node (ref "DD7") (pin "37") (pinfunction "SDA_37") (pintype "passive"))
    )
    (net (code "140") (name "unconnected-(DD7-SIM_PRESENCE-Pad34)") (class "Default")
      (node (ref "DD7") (pin "34") (pinfunction "SIM_PRESENCE_34") (pintype "passive"))
    )
    (net (code "141") (name "unconnected-(DD7-SIM_RST-Pad33)") (class "Default")
      (node (ref "DD7") (pin "33") (pinfunction "SIM_RST_33") (pintype "passive"))
    )
    (net (code "142") (name "unconnected-(DD7-VDD_EXT-Pad15)") (class "Default")
      (node (ref "DD7") (pin "15") (pinfunction "VDD_EXT_15") (pintype "passive"))
    )
    (net (code "143") (name "unconnected-(DD8-*INT-Pad1)") (class "Default")
      (node (ref "DD8") (pin "1") (pinfunction "*INT_1") (pintype "passive"))
    )
    (net (code "144") (name "unconnected-(DD8-NC-Pad3)") (class "Default")
      (node (ref "DD8") (pin "3") (pinfunction "NC_3") (pintype "passive"))
    )
    (net (code "145") (name "unconnected-(DD8-NC-Pad8)") (class "Default")
      (node (ref "DD8") (pin "8") (pinfunction "NC_8") (pintype "passive"))
    )
    (net (code "146") (name "unconnected-(DD8-NC-Pad13)") (class "Default")
      (node (ref "DD8") (pin "13") (pinfunction "NC_13") (pintype "passive"))
    )
    (net (code "147") (name "unconnected-(DD8-NC-Pad18)") (class "Default")
      (node (ref "DD8") (pin "18") (pinfunction "NC_18") (pintype "passive"))
    )
    (net (code "148") (name "unconnected-(XS2-D0-Pad7)") (class "Default")
      (node (ref "XS2") (pin "7") (pinfunction "D0_7") (pintype "passive"))
    )
    (net (code "149") (name "unconnected-(XS2-D1-Pad8)") (class "Default")
      (node (ref "XS2") (pin "8") (pinfunction "D1_8") (pintype "passive"))
    )
    (net (code "150") (name "unconnected-(XS2-D2-Pad9)") (class "Default")
      (node (ref "XS2") (pin "9") (pinfunction "D2_9") (pintype "passive"))
    )
    (net (code "151") (name "unconnected-(XS2-VO-Pad3)") (class "Default")
      (node (ref "XS2") (pin "3") (pinfunction "VO_3") (pintype "passive"))
    )
    (net (code "152") (name "unconnected-(XS4-D1-Pad8)") (class "Default")
      (node (ref "XS4") (pin "8") (pinfunction "D1_8") (pintype "passive"))
    )
    (net (code "153") (name "unconnected-(XS4-VDD-Pad2)") (class "Default")
      (node (ref "XS4") (pin "2") (pinfunction "VDD_2") (pintype "passive"))
    )
    (net (code "154") (name "unconnected-(XS8-RST-Pad2)") (class "Default")
      (node (ref "XS8") (pin "2") (pinfunction "RST_2") (pintype "passive"))
    )
    (net (code "155") (name "unconnected-(XS8-VPP-Pad5)") (class "Default")
      (node (ref "XS8") (pin "5") (pinfunction "VPP_5") (pintype "power_in"))
    )
  )
)
